# MCU.net
KiCad netlist of a schematic drawn in Altium Designer
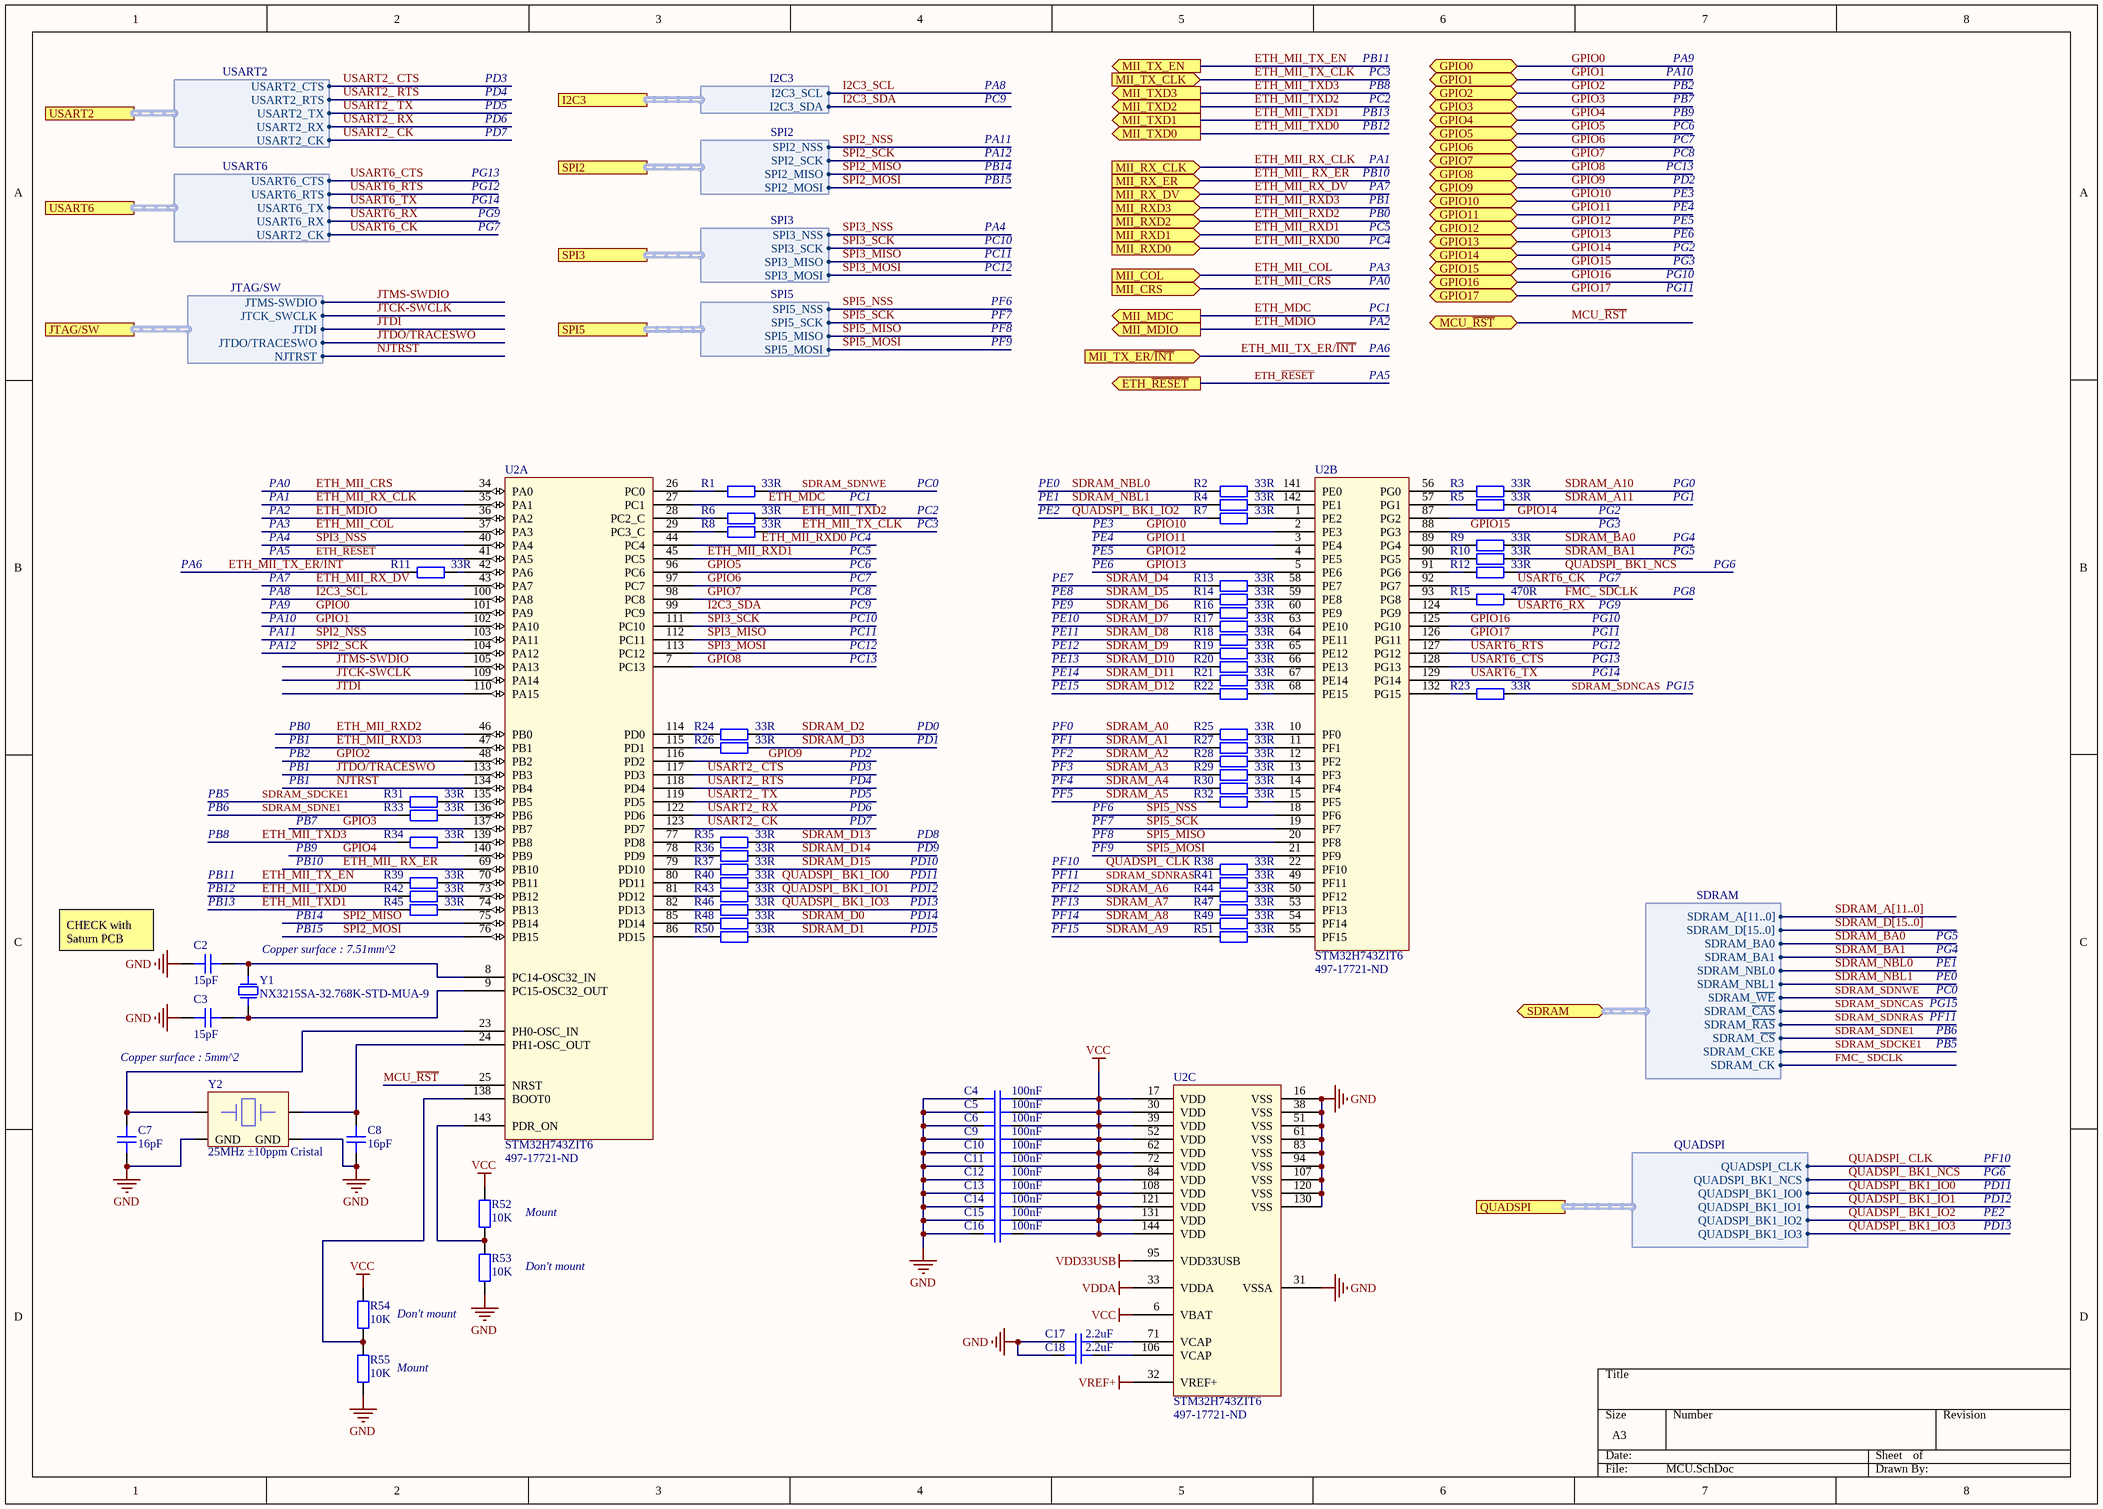
[diagram p0: MCU.SchDoc]

(export (version "E")
  (design (tool "Eeschema 10.0.6"))
  (components
    (comp (ref "C2")
      (value "15pF")
      (footprint "Capacitor-0603")
      (fields (field (name "Comment") "C-15pF-0603"))
      (libsource (lib "Components") (part "C-15pF-0603"))
    )
    (comp (ref "C3")
      (value "15pF")
      (footprint "Capacitor-0603")
      (fields (field (name "Comment") "C-15pF-0603"))
      (libsource (lib "Components") (part "C-15pF-0603"))
    )
    (comp (ref "C4")
      (value "100nF")
      (footprint "Capacitor-0603")
      (fields (field (name "Comment") "C-100nF-0603"))
      (libsource (lib "Components") (part "C-100nF-0603"))
    )
    (comp (ref "C5")
      (value "100nF")
      (footprint "Capacitor-0603")
      (fields (field (name "Comment") "C-100nF-0603"))
      (libsource (lib "Components") (part "C-100nF-0603"))
    )
    (comp (ref "C6")
      (value "100nF")
      (footprint "Capacitor-0603")
      (fields (field (name "Comment") "C-100nF-0603"))
      (libsource (lib "Components") (part "C-100nF-0603"))
    )
    (comp (ref "C7")
      (value "16pF")
      (footprint "Capacitor-0603")
      (fields (field (name "Comment") "C-16pF-0603"))
      (libsource (lib "Components") (part "C-16pF-0603"))
    )
    (comp (ref "C8")
      (value "16pF")
      (footprint "Capacitor-0603")
      (fields (field (name "Comment") "C-16pF-0603"))
      (libsource (lib "Components") (part "C-16pF-0603"))
    )
    (comp (ref "C9")
      (value "100nF")
      (footprint "Capacitor-0603")
      (fields (field (name "Comment") "C-100nF-0603"))
      (libsource (lib "Components") (part "C-100nF-0603"))
    )
    (comp (ref "C10")
      (value "100nF")
      (footprint "Capacitor-0603")
      (fields (field (name "Comment") "C-100nF-0603"))
      (libsource (lib "Components") (part "C-100nF-0603"))
    )
    (comp (ref "C11")
      (value "100nF")
      (footprint "Capacitor-0603")
      (fields (field (name "Comment") "C-100nF-0603"))
      (libsource (lib "Components") (part "C-100nF-0603"))
    )
    (comp (ref "C12")
      (value "100nF")
      (footprint "Capacitor-0603")
      (fields (field (name "Comment") "C-100nF-0603"))
      (libsource (lib "Components") (part "C-100nF-0603"))
    )
    (comp (ref "C13")
      (value "100nF")
      (footprint "Capacitor-0603")
      (fields (field (name "Comment") "C-100nF-0603"))
      (libsource (lib "Components") (part "C-100nF-0603"))
    )
    (comp (ref "C14")
      (value "100nF")
      (footprint "Capacitor-0603")
      (fields (field (name "Comment") "C-100nF-0603"))
      (libsource (lib "Components") (part "C-100nF-0603"))
    )
    (comp (ref "C15")
      (value "100nF")
      (footprint "Capacitor-0603")
      (fields (field (name "Comment") "C-100nF-0603"))
      (libsource (lib "Components") (part "C-100nF-0603"))
    )
    (comp (ref "C16")
      (value "100nF")
      (footprint "Capacitor-0603")
      (fields (field (name "Comment") "C-100nF-0603"))
      (libsource (lib "Components") (part "C-100nF-0603"))
    )
    (comp (ref "C17")
      (value "2.2uF")
      (footprint "Capacitor-0603")
      (fields (field (name "Comment") "C-2.2uF-0603"))
      (libsource (lib "Components") (part "C-2.2uF-0603"))
    )
    (comp (ref "C18")
      (value "2.2uF")
      (footprint "Capacitor-0603")
      (fields (field (name "Comment") "C-2.2uF-0603"))
      (libsource (lib "Components") (part "C-2.2uF-0603"))
    )
    (comp (ref "R1")
      (value "33R")
      (footprint "Resistor-0603")
      (fields (field (name "Comment") "R-33R-0603"))
      (libsource (lib "Components") (part "R-33R-0603"))
    )
    (comp (ref "R2")
      (value "33R")
      (footprint "Resistor-0603")
      (fields (field (name "Comment") "R-33R-0603"))
      (libsource (lib "Components") (part "R-33R-0603"))
    )
    (comp (ref "R3")
      (value "33R")
      (footprint "Resistor-0603")
      (fields (field (name "Comment") "R-33R-0603"))
      (libsource (lib "Components") (part "R-33R-0603"))
    )
    (comp (ref "R4")
      (value "33R")
      (footprint "Resistor-0603")
      (fields (field (name "Comment") "R-33R-0603"))
      (libsource (lib "Components") (part "R-33R-0603"))
    )
    (comp (ref "R5")
      (value "33R")
      (footprint "Resistor-0603")
      (fields (field (name "Comment") "R-33R-0603"))
      (libsource (lib "Components") (part "R-33R-0603"))
    )
    (comp (ref "R6")
      (value "33R")
      (footprint "Resistor-0603")
      (fields (field (name "Comment") "R-33R-0603"))
      (libsource (lib "Components") (part "R-33R-0603"))
    )
    (comp (ref "R7")
      (value "33R")
      (footprint "Resistor-0603")
      (fields (field (name "Comment") "R-33R-0603"))
      (libsource (lib "Components") (part "R-33R-0603"))
    )
    (comp (ref "R8")
      (value "33R")
      (footprint "Resistor-0603")
      (fields (field (name "Comment") "R-33R-0603"))
      (libsource (lib "Components") (part "R-33R-0603"))
    )
    (comp (ref "R9")
      (value "33R")
      (footprint "Resistor-0603")
      (fields (field (name "Comment") "R-33R-0603"))
      (libsource (lib "Components") (part "R-33R-0603"))
    )
    (comp (ref "R10")
      (value "33R")
      (footprint "Resistor-0603")
      (fields (field (name "Comment") "R-33R-0603"))
      (libsource (lib "Components") (part "R-33R-0603"))
    )
    (comp (ref "R11")
      (value "33R")
      (footprint "Resistor-0603")
      (fields (field (name "Comment") "R-33R-0603"))
      (libsource (lib "Components") (part "R-33R-0603"))
    )
    (comp (ref "R12")
      (value "33R")
      (footprint "Resistor-0603")
      (fields (field (name "Comment") "R-33R-0603"))
      (libsource (lib "Components") (part "R-33R-0603"))
    )
    (comp (ref "R13")
      (value "33R")
      (footprint "Resistor-0603")
      (fields (field (name "Comment") "R-33R-0603"))
      (libsource (lib "Components") (part "R-33R-0603"))
    )
    (comp (ref "R14")
      (value "33R")
      (footprint "Resistor-0603")
      (fields (field (name "Comment") "R-33R-0603"))
      (libsource (lib "Components") (part "R-33R-0603"))
    )
    (comp (ref "R15")
      (value "470R")
      (footprint "Resistor-0603")
      (fields (field (name "Comment") "R-470R-0603"))
      (libsource (lib "Components") (part "R-470R-0603"))
    )
    (comp (ref "R16")
      (value "33R")
      (footprint "Resistor-0603")
      (fields (field (name "Comment") "R-33R-0603"))
      (libsource (lib "Components") (part "R-33R-0603"))
    )
    (comp (ref "R17")
      (value "33R")
      (footprint "Resistor-0603")
      (fields (field (name "Comment") "R-33R-0603"))
      (libsource (lib "Components") (part "R-33R-0603"))
    )
    (comp (ref "R18")
      (value "33R")
      (footprint "Resistor-0603")
      (fields (field (name "Comment") "R-33R-0603"))
      (libsource (lib "Components") (part "R-33R-0603"))
    )
    (comp (ref "R19")
      (value "33R")
      (footprint "Resistor-0603")
      (fields (field (name "Comment") "R-33R-0603"))
      (libsource (lib "Components") (part "R-33R-0603"))
    )
    (comp (ref "R20")
      (value "33R")
      (footprint "Resistor-0603")
      (fields (field (name "Comment") "R-33R-0603"))
      (libsource (lib "Components") (part "R-33R-0603"))
    )
    (comp (ref "R21")
      (value "33R")
      (footprint "Resistor-0603")
      (fields (field (name "Comment") "R-33R-0603"))
      (libsource (lib "Components") (part "R-33R-0603"))
    )
    (comp (ref "R22")
      (value "33R")
      (footprint "Resistor-0603")
      (fields (field (name "Comment") "R-33R-0603"))
      (libsource (lib "Components") (part "R-33R-0603"))
    )
    (comp (ref "R23")
      (value "33R")
      (footprint "Resistor-0603")
      (fields (field (name "Comment") "R-33R-0603"))
      (libsource (lib "Components") (part "R-33R-0603"))
    )
    (comp (ref "R24")
      (value "33R")
      (footprint "Resistor-0603")
      (fields (field (name "Comment") "R-33R-0603"))
      (libsource (lib "Components") (part "R-33R-0603"))
    )
    (comp (ref "R25")
      (value "33R")
      (footprint "Resistor-0603")
      (fields (field (name "Comment") "R-33R-0603"))
      (libsource (lib "Components") (part "R-33R-0603"))
    )
    (comp (ref "R26")
      (value "33R")
      (footprint "Resistor-0603")
      (fields (field (name "Comment") "R-33R-0603"))
      (libsource (lib "Components") (part "R-33R-0603"))
    )
    (comp (ref "R27")
      (value "33R")
      (footprint "Resistor-0603")
      (fields (field (name "Comment") "R-33R-0603"))
      (libsource (lib "Components") (part "R-33R-0603"))
    )
    (comp (ref "R28")
      (value "33R")
      (footprint "Resistor-0603")
      (fields (field (name "Comment") "R-33R-0603"))
      (libsource (lib "Components") (part "R-33R-0603"))
    )
    (comp (ref "R29")
      (value "33R")
      (footprint "Resistor-0603")
      (fields (field (name "Comment") "R-33R-0603"))
      (libsource (lib "Components") (part "R-33R-0603"))
    )
    (comp (ref "R30")
      (value "33R")
      (footprint "Resistor-0603")
      (fields (field (name "Comment") "R-33R-0603"))
      (libsource (lib "Components") (part "R-33R-0603"))
    )
    (comp (ref "R31")
      (value "33R")
      (footprint "Resistor-0603")
      (fields (field (name "Comment") "R-33R-0603"))
      (libsource (lib "Components") (part "R-33R-0603"))
    )
    (comp (ref "R32")
      (value "33R")
      (footprint "Resistor-0603")
      (fields (field (name "Comment") "R-33R-0603"))
      (libsource (lib "Components") (part "R-33R-0603"))
    )
    (comp (ref "R33")
      (value "33R")
      (footprint "Resistor-0603")
      (fields (field (name "Comment") "R-33R-0603"))
      (libsource (lib "Components") (part "R-33R-0603"))
    )
    (comp (ref "R34")
      (value "33R")
      (footprint "Resistor-0603")
      (fields (field (name "Comment") "R-33R-0603"))
      (libsource (lib "Components") (part "R-33R-0603"))
    )
    (comp (ref "R35")
      (value "33R")
      (footprint "Resistor-0603")
      (fields (field (name "Comment") "R-33R-0603"))
      (libsource (lib "Components") (part "R-33R-0603"))
    )
    (comp (ref "R36")
      (value "33R")
      (footprint "Resistor-0603")
      (fields (field (name "Comment") "R-33R-0603"))
      (libsource (lib "Components") (part "R-33R-0603"))
    )
    (comp (ref "R37")
      (value "33R")
      (footprint "Resistor-0603")
      (fields (field (name "Comment") "R-33R-0603"))
      (libsource (lib "Components") (part "R-33R-0603"))
    )
    (comp (ref "R38")
      (value "33R")
      (footprint "Resistor-0603")
      (fields (field (name "Comment") "R-33R-0603"))
      (libsource (lib "Components") (part "R-33R-0603"))
    )
    (comp (ref "R39")
      (value "33R")
      (footprint "Resistor-0603")
      (fields (field (name "Comment") "R-33R-0603"))
      (libsource (lib "Components") (part "R-33R-0603"))
    )
    (comp (ref "R40")
      (value "33R")
      (footprint "Resistor-0603")
      (fields (field (name "Comment") "R-33R-0603"))
      (libsource (lib "Components") (part "R-33R-0603"))
    )
    (comp (ref "R41")
      (value "33R")
      (footprint "Resistor-0603")
      (fields (field (name "Comment") "R-33R-0603"))
      (libsource (lib "Components") (part "R-33R-0603"))
    )
    (comp (ref "R42")
      (value "33R")
      (footprint "Resistor-0603")
      (fields (field (name "Comment") "R-33R-0603"))
      (libsource (lib "Components") (part "R-33R-0603"))
    )
    (comp (ref "R43")
      (value "33R")
      (footprint "Resistor-0603")
      (fields (field (name "Comment") "R-33R-0603"))
      (libsource (lib "Components") (part "R-33R-0603"))
    )
    (comp (ref "R44")
      (value "33R")
      (footprint "Resistor-0603")
      (fields (field (name "Comment") "R-33R-0603"))
      (libsource (lib "Components") (part "R-33R-0603"))
    )
    (comp (ref "R45")
      (value "33R")
      (footprint "Resistor-0603")
      (fields (field (name "Comment") "R-33R-0603"))
      (libsource (lib "Components") (part "R-33R-0603"))
    )
    (comp (ref "R46")
      (value "33R")
      (footprint "Resistor-0603")
      (fields (field (name "Comment") "R-33R-0603"))
      (libsource (lib "Components") (part "R-33R-0603"))
    )
    (comp (ref "R47")
      (value "33R")
      (footprint "Resistor-0603")
      (fields (field (name "Comment") "R-33R-0603"))
      (libsource (lib "Components") (part "R-33R-0603"))
    )
    (comp (ref "R48")
      (value "33R")
      (footprint "Resistor-0603")
      (fields (field (name "Comment") "R-33R-0603"))
      (libsource (lib "Components") (part "R-33R-0603"))
    )
    (comp (ref "R49")
      (value "33R")
      (footprint "Resistor-0603")
      (fields (field (name "Comment") "R-33R-0603"))
      (libsource (lib "Components") (part "R-33R-0603"))
    )
    (comp (ref "R50")
      (value "33R")
      (footprint "Resistor-0603")
      (fields (field (name "Comment") "R-33R-0603"))
      (libsource (lib "Components") (part "R-33R-0603"))
    )
    (comp (ref "R51")
      (value "33R")
      (footprint "Resistor-0603")
      (fields (field (name "Comment") "R-33R-0603"))
      (libsource (lib "Components") (part "R-33R-0603"))
    )
    (comp (ref "R52")
      (value "10K")
      (footprint "Resistor-0603")
      (fields (field (name "Comment") "R-10K-0603"))
      (libsource (lib "Components") (part "R-10K-0603"))
    )
    (comp (ref "R53")
      (value "10K")
      (footprint "Resistor-0603")
      (fields (field (name "Comment") "R-10K-0603"))
      (libsource (lib "Components") (part "R-10K-0603"))
    )
    (comp (ref "R54")
      (value "10K")
      (footprint "Resistor-0603")
      (fields (field (name "Comment") "R-10K-0603"))
      (libsource (lib "Components") (part "R-10K-0603"))
    )
    (comp (ref "R55")
      (value "10K")
      (footprint "Resistor-0603")
      (fields (field (name "Comment") "R-10K-0603"))
      (libsource (lib "Components") (part "R-10K-0603"))
    )
    (comp (ref "U2")
      (value "STM32H743ZIT6")
      (footprint "STM32H743ZIT6")
      (fields (field (name "SUPPLIER PART NUMBER 1") "497-17721-ND"))
      (libsource (lib "Components") (part "STM32H743ZIT6"))
    )
    (comp (ref "Y1")
      (value "NX3215SA-32.768K-STD-MUA-9")
      (footprint "NX3215SA-32.768K-STD-MUA-9")
      (libsource (lib "Components") (part "NX3215SA-32.768K-STD-MUA-9"))
    )
    (comp (ref "Y2")
      (value "25MHz ±10ppm Cristal")
      (footprint "830107871909")
      (libsource (lib "Components") (part "830107871909"))
    )
  )
  (nets
    (net (code "10") (name "/ETH_MDC") (class "Default")
      (node (ref "U2") (pin "27") (pinfunction "PC1_27") (pintype "passive"))
    )
    (net (code "11") (name "/ETH_MDIO") (class "Default")
      (node (ref "U2") (pin "36") (pinfunction "PA2_36") (pintype "bidirectional"))
    )
    (net (code "12") (name "/ETH_MII_ RX_ER") (class "Default")
      (node (ref "U2") (pin "69") (pinfunction "PB10_69") (pintype "bidirectional"))
    )
    (net (code "13") (name "/ETH_MII_COL") (class "Default")
      (node (ref "U2") (pin "37") (pinfunction "PA3_37") (pintype "bidirectional"))
    )
    (net (code "14") (name "/ETH_MII_CRS") (class "Default")
      (node (ref "U2") (pin "34") (pinfunction "PA0_34") (pintype "bidirectional"))
    )
    (net (code "15") (name "/ETH_MII_RXD0") (class "Default")
      (node (ref "U2") (pin "44") (pinfunction "PC4_44") (pintype "passive"))
    )
    (net (code "16") (name "/ETH_MII_RXD1") (class "Default")
      (node (ref "U2") (pin "45") (pinfunction "PC5_45") (pintype "passive"))
    )
    (net (code "17") (name "/ETH_MII_RXD2") (class "Default")
      (node (ref "U2") (pin "46") (pinfunction "PB0_46") (pintype "bidirectional"))
    )
    (net (code "18") (name "/ETH_MII_RXD3") (class "Default")
      (node (ref "U2") (pin "47") (pinfunction "PB1_47") (pintype "bidirectional"))
    )
    (net (code "19") (name "/ETH_MII_RX_CLK") (class "Default")
      (node (ref "U2") (pin "35") (pinfunction "PA1_35") (pintype "bidirectional"))
    )
    (net (code "20") (name "/ETH_MII_RX_DV") (class "Default")
      (node (ref "U2") (pin "43") (pinfunction "PA7_43") (pintype "bidirectional"))
    )
    (net (code "21") (name "/ETH_MII_TXD0") (class "Default")
      (node (ref "R42") (pin "1") (pinfunction "1_1") (pintype "passive"))
    )
    (net (code "22") (name "/ETH_MII_TXD1") (class "Default")
      (node (ref "R45") (pin "1") (pinfunction "1_1") (pintype "passive"))
    )
    (net (code "23") (name "/ETH_MII_TXD2") (class "Default")
      (node (ref "R6") (pin "2") (pinfunction "2_2") (pintype "passive"))
    )
    (net (code "24") (name "/ETH_MII_TXD3") (class "Default")
      (node (ref "R34") (pin "1") (pinfunction "1_1") (pintype "passive"))
    )
    (net (code "25") (name "/ETH_MII_TX_CLK") (class "Default")
      (node (ref "R8") (pin "2") (pinfunction "2_2") (pintype "passive"))
    )
    (net (code "26") (name "/ETH_MII_TX_EN") (class "Default")
      (node (ref "R39") (pin "1") (pinfunction "1_1") (pintype "passive"))
    )
    (net (code "27") (name "/ETH_MII_TX_ER{slash}~{INT}") (class "Default")
      (node (ref "R11") (pin "1") (pinfunction "1_1") (pintype "passive"))
    )
    (net (code "28") (name "/ETH_~{RESET}") (class "Default")
      (node (ref "U2") (pin "41") (pinfunction "PA5_41") (pintype "bidirectional"))
    )
    (net (code "29") (name "/FMC_ SDCLK") (class "Default")
      (node (ref "R15") (pin "2") (pinfunction "2_2") (pintype "passive"))
    )
    (net (code "30") (name "/GPIO0") (class "Default")
      (node (ref "U2") (pin "101") (pinfunction "PA9_101") (pintype "bidirectional"))
    )
    (net (code "31") (name "/GPIO1") (class "Default")
      (node (ref "U2") (pin "102") (pinfunction "PA10_102") (pintype "bidirectional"))
    )
    (net (code "32") (name "/GPIO2") (class "Default")
      (node (ref "U2") (pin "48") (pinfunction "PB2_48") (pintype "bidirectional"))
    )
    (net (code "33") (name "/GPIO3") (class "Default")
      (node (ref "U2") (pin "137") (pinfunction "PB7_137") (pintype "bidirectional"))
    )
    (net (code "34") (name "/GPIO4") (class "Default")
      (node (ref "U2") (pin "140") (pinfunction "PB9_140") (pintype "bidirectional"))
    )
    (net (code "35") (name "/GPIO5") (class "Default")
      (node (ref "U2") (pin "96") (pinfunction "PC6_96") (pintype "passive"))
    )
    (net (code "36") (name "/GPIO6") (class "Default")
      (node (ref "U2") (pin "97") (pinfunction "PC7_97") (pintype "passive"))
    )
    (net (code "37") (name "/GPIO7") (class "Default")
      (node (ref "U2") (pin "98") (pinfunction "PC8_98") (pintype "passive"))
    )
    (net (code "38") (name "/GPIO8") (class "Default")
      (node (ref "U2") (pin "7") (pinfunction "PC13_7") (pintype "passive"))
    )
    (net (code "39") (name "/GPIO9") (class "Default")
      (node (ref "U2") (pin "116") (pinfunction "PD2_116") (pintype "passive"))
    )
    (net (code "40") (name "/GPIO10") (class "Default")
      (node (ref "U2") (pin "2") (pinfunction "PE3_2") (pintype "passive"))
    )
    (net (code "41") (name "/GPIO11") (class "Default")
      (node (ref "U2") (pin "3") (pinfunction "PE4_3") (pintype "passive"))
    )
    (net (code "42") (name "/GPIO12") (class "Default")
      (node (ref "U2") (pin "4") (pinfunction "PE5_4") (pintype "passive"))
    )
    (net (code "43") (name "/GPIO13") (class "Default")
      (node (ref "U2") (pin "5") (pinfunction "PE6_5") (pintype "passive"))
    )
    (net (code "44") (name "/GPIO14") (class "Default")
      (node (ref "U2") (pin "87") (pinfunction "PG2_87") (pintype "passive"))
    )
    (net (code "45") (name "/GPIO15") (class "Default")
      (node (ref "U2") (pin "88") (pinfunction "PG3_88") (pintype "passive"))
    )
    (net (code "46") (name "/GPIO16") (class "Default")
      (node (ref "U2") (pin "125") (pinfunction "PG10_125") (pintype "passive"))
    )
    (net (code "47") (name "/GPIO17") (class "Default")
      (node (ref "U2") (pin "126") (pinfunction "PG11_126") (pintype "passive"))
    )
    (net (code "48") (name "/I2C3_SCL") (class "Default")
      (node (ref "U2") (pin "100") (pinfunction "PA8_100") (pintype "bidirectional"))
    )
    (net (code "49") (name "/I2C3_SDA") (class "Default")
      (node (ref "U2") (pin "99") (pinfunction "PC9_99") (pintype "passive"))
    )
    (net (code "50") (name "/JTCK-SWCLK") (class "Default")
      (node (ref "U2") (pin "109") (pinfunction "PA14_109") (pintype "bidirectional"))
    )
    (net (code "51") (name "/JTDI") (class "Default")
      (node (ref "U2") (pin "110") (pinfunction "PA15_110") (pintype "bidirectional"))
    )
    (net (code "52") (name "/JTDO{slash}TRACESWO") (class "Default")
      (node (ref "U2") (pin "133") (pinfunction "PB3_133") (pintype "bidirectional"))
    )
    (net (code "53") (name "/JTMS-SWDIO") (class "Default")
      (node (ref "U2") (pin "105") (pinfunction "PA13_105") (pintype "bidirectional"))
    )
    (net (code "54") (name "/MCU_~{RST}") (class "Default")
      (node (ref "U2") (pin "25") (pinfunction "NRST_25") (pintype "passive"))
    )
    (net (code "55") (name "/NJTRST") (class "Default")
      (node (ref "U2") (pin "134") (pinfunction "PB4_134") (pintype "bidirectional"))
    )
    (net (code "56") (name "/QUADSPI_ BK1_IO0") (class "Default")
      (node (ref "R40") (pin "2") (pinfunction "2_2") (pintype "passive"))
    )
    (net (code "57") (name "/QUADSPI_ BK1_IO1") (class "Default")
      (node (ref "R43") (pin "2") (pinfunction "2_2") (pintype "passive"))
    )
    (net (code "58") (name "/QUADSPI_ BK1_IO2") (class "Default")
      (node (ref "R7") (pin "1") (pinfunction "1_1") (pintype "passive"))
    )
    (net (code "59") (name "/QUADSPI_ BK1_IO3") (class "Default")
      (node (ref "R46") (pin "2") (pinfunction "2_2") (pintype "passive"))
    )
    (net (code "60") (name "/QUADSPI_ BK1_NCS") (class "Default")
      (node (ref "R12") (pin "2") (pinfunction "2_2") (pintype "passive"))
    )
    (net (code "61") (name "/QUADSPI_ CLK") (class "Default")
      (node (ref "R38") (pin "1") (pinfunction "1_1") (pintype "passive"))
    )
    (net (code "62") (name "/SDRAM_A0") (class "Default")
      (node (ref "R25") (pin "1") (pinfunction "1_1") (pintype "passive"))
    )
    (net (code "63") (name "/SDRAM_A1") (class "Default")
      (node (ref "R27") (pin "1") (pinfunction "1_1") (pintype "passive"))
    )
    (net (code "64") (name "/SDRAM_A2") (class "Default")
      (node (ref "R28") (pin "1") (pinfunction "1_1") (pintype "passive"))
    )
    (net (code "65") (name "/SDRAM_A3") (class "Default")
      (node (ref "R29") (pin "1") (pinfunction "1_1") (pintype "passive"))
    )
    (net (code "66") (name "/SDRAM_A4") (class "Default")
      (node (ref "R30") (pin "1") (pinfunction "1_1") (pintype "passive"))
    )
    (net (code "67") (name "/SDRAM_A5") (class "Default")
      (node (ref "R32") (pin "1") (pinfunction "1_1") (pintype "passive"))
    )
    (net (code "68") (name "/SDRAM_A6") (class "Default")
      (node (ref "R44") (pin "1") (pinfunction "1_1") (pintype "passive"))
    )
    (net (code "69") (name "/SDRAM_A7") (class "Default")
      (node (ref "R47") (pin "1") (pinfunction "1_1") (pintype "passive"))
    )
    (net (code "70") (name "/SDRAM_A8") (class "Default")
      (node (ref "R49") (pin "1") (pinfunction "1_1") (pintype "passive"))
    )
    (net (code "71") (name "/SDRAM_A9") (class "Default")
      (node (ref "R51") (pin "1") (pinfunction "1_1") (pintype "passive"))
    )
    (net (code "72") (name "/SDRAM_A10") (class "Default")
      (node (ref "R3") (pin "2") (pinfunction "2_2") (pintype "passive"))
    )
    (net (code "73") (name "/SDRAM_A11") (class "Default")
      (node (ref "R5") (pin "2") (pinfunction "2_2") (pintype "passive"))
    )
    (net (code "75") (name "/SDRAM_BA0") (class "Default")
      (node (ref "R9") (pin "2") (pinfunction "2_2") (pintype "passive"))
    )
    (net (code "76") (name "/SDRAM_BA1") (class "Default")
      (node (ref "R10") (pin "2") (pinfunction "2_2") (pintype "passive"))
    )
    (net (code "77") (name "/SDRAM_D0") (class "Default")
      (node (ref "R48") (pin "2") (pinfunction "2_2") (pintype "passive"))
    )
    (net (code "78") (name "/SDRAM_D1") (class "Default")
      (node (ref "R50") (pin "2") (pinfunction "2_2") (pintype "passive"))
    )
    (net (code "79") (name "/SDRAM_D2") (class "Default")
      (node (ref "R24") (pin "2") (pinfunction "2_2") (pintype "passive"))
    )
    (net (code "80") (name "/SDRAM_D3") (class "Default")
      (node (ref "R26") (pin "2") (pinfunction "2_2") (pintype "passive"))
    )
    (net (code "81") (name "/SDRAM_D4") (class "Default")
      (node (ref "R13") (pin "1") (pinfunction "1_1") (pintype "passive"))
    )
    (net (code "82") (name "/SDRAM_D5") (class "Default")
      (node (ref "R14") (pin "1") (pinfunction "1_1") (pintype "passive"))
    )
    (net (code "83") (name "/SDRAM_D6") (class "Default")
      (node (ref "R16") (pin "1") (pinfunction "1_1") (pintype "passive"))
    )
    (net (code "84") (name "/SDRAM_D7") (class "Default")
      (node (ref "R17") (pin "1") (pinfunction "1_1") (pintype "passive"))
    )
    (net (code "85") (name "/SDRAM_D8") (class "Default")
      (node (ref "R18") (pin "1") (pinfunction "1_1") (pintype "passive"))
    )
    (net (code "86") (name "/SDRAM_D9") (class "Default")
      (node (ref "R19") (pin "1") (pinfunction "1_1") (pintype "passive"))
    )
    (net (code "87") (name "/SDRAM_D10") (class "Default")
      (node (ref "R20") (pin "1") (pinfunction "1_1") (pintype "passive"))
    )
    (net (code "88") (name "/SDRAM_D11") (class "Default")
      (node (ref "R21") (pin "1") (pinfunction "1_1") (pintype "passive"))
    )
    (net (code "89") (name "/SDRAM_D12") (class "Default")
      (node (ref "R22") (pin "1") (pinfunction "1_1") (pintype "passive"))
    )
    (net (code "90") (name "/SDRAM_D13") (class "Default")
      (node (ref "R35") (pin "2") (pinfunction "2_2") (pintype "passive"))
    )
    (net (code "91") (name "/SDRAM_D14") (class "Default")
      (node (ref "R36") (pin "2") (pinfunction "2_2") (pintype "passive"))
    )
    (net (code "92") (name "/SDRAM_D15") (class "Default")
      (node (ref "R37") (pin "2") (pinfunction "2_2") (pintype "passive"))
    )
    (net (code "94") (name "/SDRAM_NBL0") (class "Default")
      (node (ref "R2") (pin "1") (pinfunction "1_1") (pintype "passive"))
    )
    (net (code "95") (name "/SDRAM_NBL1") (class "Default")
      (node (ref "R4") (pin "1") (pinfunction "1_1") (pintype "passive"))
    )
    (net (code "96") (name "/SDRAM_SDCKE1") (class "Default")
      (node (ref "R31") (pin "1") (pinfunction "1_1") (pintype "passive"))
    )
    (net (code "97") (name "/SDRAM_SDNCAS") (class "Default")
      (node (ref "R23") (pin "2") (pinfunction "2_2") (pintype "passive"))
    )
    (net (code "98") (name "/SDRAM_SDNE1") (class "Default")
      (node (ref "R33") (pin "1") (pinfunction "1_1") (pintype "passive"))
    )
    (net (code "99") (name "/SDRAM_SDNRAS") (class "Default")
      (node (ref "R41") (pin "1") (pinfunction "1_1") (pintype "passive"))
    )
    (net (code "100") (name "/SDRAM_SDNWE") (class "Default")
      (node (ref "R1") (pin "2") (pinfunction "2_2") (pintype "passive"))
    )
    (net (code "101") (name "/SPI2_MISO") (class "Default")
      (node (ref "U2") (pin "75") (pinfunction "PB14_75") (pintype "bidirectional"))
    )
    (net (code "102") (name "/SPI2_MOSI") (class "Default")
      (node (ref "U2") (pin "76") (pinfunction "PB15_76") (pintype "bidirectional"))
    )
    (net (code "103") (name "/SPI2_NSS") (class "Default")
      (node (ref "U2") (pin "103") (pinfunction "PA11_103") (pintype "bidirectional"))
    )
    (net (code "104") (name "/SPI2_SCK") (class "Default")
      (node (ref "U2") (pin "104") (pinfunction "PA12_104") (pintype "bidirectional"))
    )
    (net (code "105") (name "/SPI3_MISO") (class "Default")
      (node (ref "U2") (pin "112") (pinfunction "PC11_112") (pintype "passive"))
    )
    (net (code "106") (name "/SPI3_MOSI") (class "Default")
      (node (ref "U2") (pin "113") (pinfunction "PC12_113") (pintype "passive"))
    )
    (net (code "107") (name "/SPI3_NSS") (class "Default")
      (node (ref "U2") (pin "40") (pinfunction "PA4_40") (pintype "bidirectional"))
    )
    (net (code "108") (name "/SPI3_SCK") (class "Default")
      (node (ref "U2") (pin "111") (pinfunction "PC10_111") (pintype "passive"))
    )
    (net (code "109") (name "/SPI5_MISO") (class "Default")
      (node (ref "U2") (pin "20") (pinfunction "PF8_20") (pintype "passive"))
    )
    (net (code "110") (name "/SPI5_MOSI") (class "Default")
      (node (ref "U2") (pin "21") (pinfunction "PF9_21") (pintype "passive"))
    )
    (net (code "111") (name "/SPI5_NSS") (class "Default")
      (node (ref "U2") (pin "18") (pinfunction "PF6_18") (pintype "passive"))
    )
    (net (code "112") (name "/SPI5_SCK") (class "Default")
      (node (ref "U2") (pin "19") (pinfunction "PF7_19") (pintype "passive"))
    )
    (net (code "113") (name "/USART2_ CK") (class "Default")
      (node (ref "U2") (pin "123") (pinfunction "PD7_123") (pintype "passive"))
    )
    (net (code "114") (name "/USART2_ CTS") (class "Default")
      (node (ref "U2") (pin "117") (pinfunction "PD3_117") (pintype "passive"))
    )
    (net (code "115") (name "/USART2_ RTS") (class "Default")
      (node (ref "U2") (pin "118") (pinfunction "PD4_118") (pintype "passive"))
    )
    (net (code "116") (name "/USART2_ RX") (class "Default")
      (node (ref "U2") (pin "122") (pinfunction "PD6_122") (pintype "passive"))
    )
    (net (code "117") (name "/USART2_ TX") (class "Default")
      (node (ref "U2") (pin "119") (pinfunction "PD5_119") (pintype "passive"))
    )
    (net (code "118") (name "/USART6_CK") (class "Default")
      (node (ref "U2") (pin "92") (pinfunction "PG7_92") (pintype "passive"))
    )
    (net (code "119") (name "/USART6_CTS") (class "Default")
      (node (ref "U2") (pin "128") (pinfunction "PG13_128") (pintype "passive"))
    )
    (net (code "120") (name "/USART6_RTS") (class "Default")
      (node (ref "U2") (pin "127") (pinfunction "PG12_127") (pintype "passive"))
    )
    (net (code "121") (name "/USART6_RX") (class "Default")
      (node (ref "U2") (pin "124") (pinfunction "PG9_124") (pintype "passive"))
    )
    (net (code "122") (name "/USART6_TX") (class "Default")
      (node (ref "U2") (pin "129") (pinfunction "PG14_129") (pintype "passive"))
    )
    (net (code "132") (name "GND") (class "Default")
      (node (ref "C10") (pin "1") (pinfunction "1_1") (pintype "passive"))
      (node (ref "C11") (pin "1") (pinfunction "1_1") (pintype "passive"))
      (node (ref "C12") (pin "1") (pinfunction "1_1") (pintype "passive"))
      (node (ref "C13") (pin "1") (pinfunction "1_1") (pintype "passive"))
      (node (ref "C14") (pin "1") (pinfunction "1_1") (pintype "passive"))
      (node (ref "C15") (pin "1") (pinfunction "1_1") (pintype "passive"))
      (node (ref "C16") (pin "1") (pinfunction "1_1") (pintype "passive"))
      (node (ref "C17") (pin "1") (pinfunction "1_1") (pintype "passive"))
      (node (ref "C18") (pin "1") (pinfunction "1_1") (pintype "passive"))
      (node (ref "C2") (pin "1") (pinfunction "1_1") (pintype "passive"))
      (node (ref "C3") (pin "1") (pinfunction "1_1") (pintype "passive"))
      (node (ref "C4") (pin "1") (pinfunction "1_1") (pintype "passive"))
      (node (ref "C5") (pin "1") (pinfunction "1_1") (pintype "passive"))
      (node (ref "C6") (pin "1") (pinfunction "1_1") (pintype "passive"))
      (node (ref "C7") (pin "1") (pinfunction "1_1") (pintype "passive"))
      (node (ref "C8") (pin "1") (pinfunction "1_1") (pintype "passive"))
      (node (ref "C9") (pin "1") (pinfunction "1_1") (pintype "passive"))
      (node (ref "R53") (pin "1") (pinfunction "1_1") (pintype "passive"))
      (node (ref "R55") (pin "1") (pinfunction "1_1") (pintype "passive"))
      (node (ref "U2") (pin "107") (pinfunction "VSS_107") (pintype "passive"))
      (node (ref "U2") (pin "120") (pinfunction "VSS_120") (pintype "passive"))
      (node (ref "U2") (pin "130") (pinfunction "VSS_130") (pintype "passive"))
      (node (ref "U2") (pin "16") (pinfunction "VSS_16") (pintype "passive"))
      (node (ref "U2") (pin "31") (pinfunction "VSSA_31") (pintype "passive"))
      (node (ref "U2") (pin "38") (pinfunction "VSS_38") (pintype "passive"))
      (node (ref "U2") (pin "51") (pinfunction "VSS_51") (pintype "passive"))
      (node (ref "U2") (pin "61") (pinfunction "VSS_61") (pintype "passive"))
      (node (ref "U2") (pin "83") (pinfunction "VSS_83") (pintype "passive"))
      (node (ref "U2") (pin "94") (pinfunction "VSS_94") (pintype "passive"))
      (node (ref "Y2") (pin "2") (pinfunction "GND_2") (pintype "passive"))
      (node (ref "Y2") (pin "4") (pinfunction "GND_4") (pintype "passive"))
    )
    (net (code "133") (name "Net-(C17-Pad2)") (class "Default")
      (node (ref "C17") (pin "2") (pinfunction "2_2") (pintype "passive"))
      (node (ref "U2") (pin "71") (pinfunction "VCAP_71") (pintype "passive"))
    )
    (net (code "134") (name "Net-(C18-Pad2)") (class "Default")
      (node (ref "C18") (pin "2") (pinfunction "2_2") (pintype "passive"))
      (node (ref "U2") (pin "106") (pinfunction "VCAP_106") (pintype "passive"))
    )
    (net (code "135") (name "Net-(U2A-BOOT0)") (class "Default")
      (node (ref "R54") (pin "1") (pinfunction "1_1") (pintype "passive"))
      (node (ref "R55") (pin "2") (pinfunction "2_2") (pintype "passive"))
      (node (ref "U2") (pin "138") (pinfunction "BOOT0_138") (pintype "passive"))
    )
    (net (code "136") (name "Net-(U2A-PA6)") (class "Default")
      (node (ref "R11") (pin "2") (pinfunction "2_2") (pintype "passive"))
      (node (ref "U2") (pin "42") (pinfunction "PA6_42") (pintype "bidirectional"))
    )
    (net (code "137") (name "Net-(U2A-PB5)") (class "Default")
      (node (ref "R31") (pin "2") (pinfunction "2_2") (pintype "passive"))
      (node (ref "U2") (pin "135") (pinfunction "PB5_135") (pintype "bidirectional"))
    )
    (net (code "138") (name "Net-(U2A-PB6)") (class "Default")
      (node (ref "R33") (pin "2") (pinfunction "2_2") (pintype "passive"))
      (node (ref "U2") (pin "136") (pinfunction "PB6_136") (pintype "bidirectional"))
    )
    (net (code "139") (name "Net-(U2A-PB8)") (class "Default")
      (node (ref "R34") (pin "2") (pinfunction "2_2") (pintype "passive"))
      (node (ref "U2") (pin "139") (pinfunction "PB8_139") (pintype "bidirectional"))
    )
    (net (code "140") (name "Net-(U2A-PB11)") (class "Default")
      (node (ref "R39") (pin "2") (pinfunction "2_2") (pintype "passive"))
      (node (ref "U2") (pin "70") (pinfunction "PB11_70") (pintype "bidirectional"))
    )
    (net (code "141") (name "Net-(U2A-PB12)") (class "Default")
      (node (ref "R42") (pin "2") (pinfunction "2_2") (pintype "passive"))
      (node (ref "U2") (pin "73") (pinfunction "PB12_73") (pintype "bidirectional"))
    )
    (net (code "142") (name "Net-(U2A-PB13)") (class "Default")
      (node (ref "R45") (pin "2") (pinfunction "2_2") (pintype "passive"))
      (node (ref "U2") (pin "74") (pinfunction "PB13_74") (pintype "bidirectional"))
    )
    (net (code "143") (name "Net-(U2A-PC0)") (class "Default")
      (node (ref "R1") (pin "1") (pinfunction "1_1") (pintype "passive"))
      (node (ref "U2") (pin "26") (pinfunction "PC0_26") (pintype "passive"))
    )
    (net (code "144") (name "Net-(U2A-PC2_C)") (class "Default")
      (node (ref "R6") (pin "1") (pinfunction "1_1") (pintype "passive"))
      (node (ref "U2") (pin "28") (pinfunction "PC2_C_28") (pintype "passive"))
    )
    (net (code "145") (name "Net-(U2A-PC3_C)") (class "Default")
      (node (ref "R8") (pin "1") (pinfunction "1_1") (pintype "passive"))
      (node (ref "U2") (pin "29") (pinfunction "PC3_C_29") (pintype "passive"))
    )
    (net (code "146") (name "Net-(U2A-PC14-OSC32_IN)") (class "Default")
      (node (ref "C2") (pin "2") (pinfunction "2_2") (pintype "passive"))
      (node (ref "U2") (pin "8") (pinfunction "PC14-OSC32_IN_8") (pintype "passive"))
      (node (ref "Y1") (pin "2") (pinfunction "2_2") (pintype "passive"))
    )
    (net (code "147") (name "Net-(U2A-PC15-OSC32_OUT)") (class "Default")
      (node (ref "C3") (pin "2") (pinfunction "2_2") (pintype "passive"))
      (node (ref "U2") (pin "9") (pinfunction "PC15-OSC32_OUT_9") (pintype "passive"))
      (node (ref "Y1") (pin "1") (pinfunction "1_1") (pintype "passive"))
    )
    (net (code "148") (name "Net-(U2A-PD0)") (class "Default")
      (node (ref "R24") (pin "1") (pinfunction "1_1") (pintype "passive"))
      (node (ref "U2") (pin "114") (pinfunction "PD0_114") (pintype "passive"))
    )
    (net (code "149") (name "Net-(U2A-PD1)") (class "Default")
      (node (ref "R26") (pin "1") (pinfunction "1_1") (pintype "passive"))
      (node (ref "U2") (pin "115") (pinfunction "PD1_115") (pintype "passive"))
    )
    (net (code "150") (name "Net-(U2A-PD8)") (class "Default")
      (node (ref "R35") (pin "1") (pinfunction "1_1") (pintype "passive"))
      (node (ref "U2") (pin "77") (pinfunction "PD8_77") (pintype "passive"))
    )
    (net (code "151") (name "Net-(U2A-PD9)") (class "Default")
      (node (ref "R36") (pin "1") (pinfunction "1_1") (pintype "passive"))
      (node (ref "U2") (pin "78") (pinfunction "PD9_78") (pintype "passive"))
    )
    (net (code "152") (name "Net-(U2A-PD10)") (class "Default")
      (node (ref "R37") (pin "1") (pinfunction "1_1") (pintype "passive"))
      (node (ref "U2") (pin "79") (pinfunction "PD10_79") (pintype "passive"))
    )
    (net (code "153") (name "Net-(U2A-PD11)") (class "Default")
      (node (ref "R40") (pin "1") (pinfunction "1_1") (pintype "passive"))
      (node (ref "U2") (pin "80") (pinfunction "PD11_80") (pintype "passive"))
    )
    (net (code "154") (name "Net-(U2A-PD12)") (class "Default")
      (node (ref "R43") (pin "1") (pinfunction "1_1") (pintype "passive"))
      (node (ref "U2") (pin "81") (pinfunction "PD12_81") (pintype "passive"))
    )
    (net (code "155") (name "Net-(U2A-PD13)") (class "Default")
      (node (ref "R46") (pin "1") (pinfunction "1_1") (pintype "passive"))
      (node (ref "U2") (pin "82") (pinfunction "PD13_82") (pintype "passive"))
    )
    (net (code "156") (name "Net-(U2A-PD14)") (class "Default")
      (node (ref "R48") (pin "1") (pinfunction "1_1") (pintype "passive"))
      (node (ref "U2") (pin "85") (pinfunction "PD14_85") (pintype "passive"))
    )
    (net (code "157") (name "Net-(U2A-PD15)") (class "Default")
      (node (ref "R50") (pin "1") (pinfunction "1_1") (pintype "passive"))
      (node (ref "U2") (pin "86") (pinfunction "PD15_86") (pintype "passive"))
    )
    (net (code "158") (name "Net-(U2A-PDR_ON)") (class "Default")
      (node (ref "R52") (pin "1") (pinfunction "1_1") (pintype "passive"))
      (node (ref "R53") (pin "2") (pinfunction "2_2") (pintype "passive"))
      (node (ref "U2") (pin "143") (pinfunction "PDR_ON_143") (pintype "passive"))
    )
    (net (code "159") (name "Net-(U2A-PH0-OSC_IN)") (class "Default")
      (node (ref "C7") (pin "2") (pinfunction "2_2") (pintype "passive"))
      (node (ref "U2") (pin "23") (pinfunction "PH0-OSC_IN_23") (pintype "passive"))
      (node (ref "Y2") (pin "1") (pinfunction "GND_1") (pintype "passive"))
    )
    (net (code "160") (name "Net-(U2A-PH1-OSC_OUT)") (class "Default")
      (node (ref "C8") (pin "2") (pinfunction "2_2") (pintype "passive"))
      (node (ref "U2") (pin "24") (pinfunction "PH1-OSC_OUT_24") (pintype "passive"))
      (node (ref "Y2") (pin "3") (pinfunction "XTAL2_3") (pintype "passive"))
    )
    (net (code "161") (name "Net-(U2B-PE0)") (class "Default")
      (node (ref "R2") (pin "2") (pinfunction "2_2") (pintype "passive"))
      (node (ref "U2") (pin "141") (pinfunction "PE0_141") (pintype "passive"))
    )
    (net (code "162") (name "Net-(U2B-PE1)") (class "Default")
      (node (ref "R4") (pin "2") (pinfunction "2_2") (pintype "passive"))
      (node (ref "U2") (pin "142") (pinfunction "PE1_142") (pintype "passive"))
    )
    (net (code "163") (name "Net-(U2B-PE2)") (class "Default")
      (node (ref "R7") (pin "2") (pinfunction "2_2") (pintype "passive"))
      (node (ref "U2") (pin "1") (pinfunction "PE2_1") (pintype "passive"))
    )
    (net (code "164") (name "Net-(U2B-PE7)") (class "Default")
      (node (ref "R13") (pin "2") (pinfunction "2_2") (pintype "passive"))
      (node (ref "U2") (pin "58") (pinfunction "PE7_58") (pintype "passive"))
    )
    (net (code "165") (name "Net-(U2B-PE8)") (class "Default")
      (node (ref "R14") (pin "2") (pinfunction "2_2") (pintype "passive"))
      (node (ref "U2") (pin "59") (pinfunction "PE8_59") (pintype "passive"))
    )
    (net (code "166") (name "Net-(U2B-PE9)") (class "Default")
      (node (ref "R16") (pin "2") (pinfunction "2_2") (pintype "passive"))
      (node (ref "U2") (pin "60") (pinfunction "PE9_60") (pintype "passive"))
    )
    (net (code "167") (name "Net-(U2B-PE10)") (class "Default")
      (node (ref "R17") (pin "2") (pinfunction "2_2") (pintype "passive"))
      (node (ref "U2") (pin "63") (pinfunction "PE10_63") (pintype "passive"))
    )
    (net (code "168") (name "Net-(U2B-PE11)") (class "Default")
      (node (ref "R18") (pin "2") (pinfunction "2_2") (pintype "passive"))
      (node (ref "U2") (pin "64") (pinfunction "PE11_64") (pintype "passive"))
    )
    (net (code "169") (name "Net-(U2B-PE12)") (class "Default")
      (node (ref "R19") (pin "2") (pinfunction "2_2") (pintype "passive"))
      (node (ref "U2") (pin "65") (pinfunction "PE12_65") (pintype "passive"))
    )
    (net (code "170") (name "Net-(U2B-PE13)") (class "Default")
      (node (ref "R20") (pin "2") (pinfunction "2_2") (pintype "passive"))
      (node (ref "U2") (pin "66") (pinfunction "PE13_66") (pintype "passive"))
    )
    (net (code "171") (name "Net-(U2B-PE14)") (class "Default")
      (node (ref "R21") (pin "2") (pinfunction "2_2") (pintype "passive"))
      (node (ref "U2") (pin "67") (pinfunction "PE14_67") (pintype "passive"))
    )
    (net (code "172") (name "Net-(U2B-PE15)") (class "Default")
      (node (ref "R22") (pin "2") (pinfunction "2_2") (pintype "passive"))
      (node (ref "U2") (pin "68") (pinfunction "PE15_68") (pintype "passive"))
    )
    (net (code "173") (name "Net-(U2B-PF0)") (class "Default")
      (node (ref "R25") (pin "2") (pinfunction "2_2") (pintype "passive"))
      (node (ref "U2") (pin "10") (pinfunction "PF0_10") (pintype "passive"))
    )
    (net (code "174") (name "Net-(U2B-PF1)") (class "Default")
      (node (ref "R27") (pin "2") (pinfunction "2_2") (pintype "passive"))
      (node (ref "U2") (pin "11") (pinfunction "PF1_11") (pintype "passive"))
    )
    (net (code "175") (name "Net-(U2B-PF2)") (class "Default")
      (node (ref "R28") (pin "2") (pinfunction "2_2") (pintype "passive"))
      (node (ref "U2") (pin "12") (pinfunction "PF2_12") (pintype "passive"))
    )
    (net (code "176") (name "Net-(U2B-PF3)") (class "Default")
      (node (ref "R29") (pin "2") (pinfunction "2_2") (pintype "passive"))
      (node (ref "U2") (pin "13") (pinfunction "PF3_13") (pintype "passive"))
    )
    (net (code "177") (name "Net-(U2B-PF4)") (class "Default")
      (node (ref "R30") (pin "2") (pinfunction "2_2") (pintype "passive"))
      (node (ref "U2") (pin "14") (pinfunction "PF4_14") (pintype "passive"))
    )
    (net (code "178") (name "Net-(U2B-PF5)") (class "Default")
      (node (ref "R32") (pin "2") (pinfunction "2_2") (pintype "passive"))
      (node (ref "U2") (pin "15") (pinfunction "PF5_15") (pintype "passive"))
    )
    (net (code "179") (name "Net-(U2B-PF10)") (class "Default")
      (node (ref "R38") (pin "2") (pinfunction "2_2") (pintype "passive"))
      (node (ref "U2") (pin "22") (pinfunction "PF10_22") (pintype "passive"))
    )
    (net (code "180") (name "Net-(U2B-PF11)") (class "Default")
      (node (ref "R41") (pin "2") (pinfunction "2_2") (pintype "passive"))
      (node (ref "U2") (pin "49") (pinfunction "PF11_49") (pintype "passive"))
    )
    (net (code "181") (name "Net-(U2B-PF12)") (class "Default")
      (node (ref "R44") (pin "2") (pinfunction "2_2") (pintype "passive"))
      (node (ref "U2") (pin "50") (pinfunction "PF12_50") (pintype "passive"))
    )
    (net (code "182") (name "Net-(U2B-PF13)") (class "Default")
      (node (ref "R47") (pin "2") (pinfunction "2_2") (pintype "passive"))
      (node (ref "U2") (pin "53") (pinfunction "PF13_53") (pintype "passive"))
    )
    (net (code "183") (name "Net-(U2B-PF14)") (class "Default")
      (node (ref "R49") (pin "2") (pinfunction "2_2") (pintype "passive"))
      (node (ref "U2") (pin "54") (pinfunction "PF14_54") (pintype "passive"))
    )
    (net (code "184") (name "Net-(U2B-PF15)") (class "Default")
      (node (ref "R51") (pin "2") (pinfunction "2_2") (pintype "passive"))
      (node (ref "U2") (pin "55") (pinfunction "PF15_55") (pintype "passive"))
    )
    (net (code "185") (name "Net-(U2B-PG0)") (class "Default")
      (node (ref "R3") (pin "1") (pinfunction "1_1") (pintype "passive"))
      (node (ref "U2") (pin "56") (pinfunction "PG0_56") (pintype "passive"))
    )
    (net (code "186") (name "Net-(U2B-PG1)") (class "Default")
      (node (ref "R5") (pin "1") (pinfunction "1_1") (pintype "passive"))
      (node (ref "U2") (pin "57") (pinfunction "PG1_57") (pintype "passive"))
    )
    (net (code "187") (name "Net-(U2B-PG4)") (class "Default")
      (node (ref "R9") (pin "1") (pinfunction "1_1") (pintype "passive"))
      (node (ref "U2") (pin "89") (pinfunction "PG4_89") (pintype "passive"))
    )
    (net (code "188") (name "Net-(U2B-PG5)") (class "Default")
      (node (ref "R10") (pin "1") (pinfunction "1_1") (pintype "passive"))
      (node (ref "U2") (pin "90") (pinfunction "PG5_90") (pintype "passive"))
    )
    (net (code "189") (name "Net-(U2B-PG6)") (class "Default")
      (node (ref "R12") (pin "1") (pinfunction "1_1") (pintype "passive"))
      (node (ref "U2") (pin "91") (pinfunction "PG6_91") (pintype "passive"))
    )
    (net (code "190") (name "Net-(U2B-PG8)") (class "Default")
      (node (ref "R15") (pin "1") (pinfunction "1_1") (pintype "passive"))
      (node (ref "U2") (pin "93") (pinfunction "PG8_93") (pintype "passive"))
    )
    (net (code "191") (name "Net-(U2B-PG15)") (class "Default")
      (node (ref "R23") (pin "1") (pinfunction "1_1") (pintype "passive"))
      (node (ref "U2") (pin "132") (pinfunction "PG15_132") (pintype "passive"))
    )
    (net (code "192") (name "VCC") (class "Default")
      (node (ref "C10") (pin "2") (pinfunction "2_2") (pintype "passive"))
      (node (ref "C11") (pin "2") (pinfunction "2_2") (pintype "passive"))
      (node (ref "C12") (pin "2") (pinfunction "2_2") (pintype "passive"))
      (node (ref "C13") (pin "2") (pinfunction "2_2") (pintype "passive"))
      (node (ref "C14") (pin "2") (pinfunction "2_2") (pintype "passive"))
      (node (ref "C15") (pin "2") (pinfunction "2_2") (pintype "passive"))
      (node (ref "C16") (pin "2") (pinfunction "2_2") (pintype "passive"))
      (node (ref "C4") (pin "2") (pinfunction "2_2") (pintype "passive"))
      (node (ref "C5") (pin "2") (pinfunction "2_2") (pintype "passive"))
      (node (ref "C6") (pin "2") (pinfunction "2_2") (pintype "passive"))
      (node (ref "C9") (pin "2") (pinfunction "2_2") (pintype "passive"))
      (node (ref "R52") (pin "2") (pinfunction "2_2") (pintype "passive"))
      (node (ref "R54") (pin "2") (pinfunction "2_2") (pintype "passive"))
      (node (ref "U2") (pin "108") (pinfunction "VDD_108") (pintype "passive"))
      (node (ref "U2") (pin "121") (pinfunction "VDD_121") (pintype "passive"))
      (node (ref "U2") (pin "131") (pinfunction "VDD_131") (pintype "passive"))
      (node (ref "U2") (pin "144") (pinfunction "VDD_144") (pintype "passive"))
      (node (ref "U2") (pin "17") (pinfunction "VDD_17") (pintype "passive"))
      (node (ref "U2") (pin "30") (pinfunction "VDD_30") (pintype "passive"))
      (node (ref "U2") (pin "39") (pinfunction "VDD_39") (pintype "passive"))
      (node (ref "U2") (pin "52") (pinfunction "VDD_52") (pintype "passive"))
      (node (ref "U2") (pin "6") (pinfunction "VBAT_6") (pintype "passive"))
      (node (ref "U2") (pin "62") (pinfunction "VDD_62") (pintype "passive"))
      (node (ref "U2") (pin "72") (pinfunction "VDD_72") (pintype "passive"))
      (node (ref "U2") (pin "84") (pinfunction "VDD_84") (pintype "passive"))
    )
    (net (code "193") (name "VDD33USB") (class "Default")
      (node (ref "U2") (pin "95") (pinfunction "VDD33USB_95") (pintype "passive"))
    )
    (net (code "194") (name "VDDA") (class "Default")
      (node (ref "U2") (pin "33") (pinfunction "VDDA_33") (pintype "passive"))
    )
    (net (code "195") (name "VREF+") (class "Default")
      (node (ref "U2") (pin "32") (pinfunction "VREF+_32") (pintype "passive"))
    )
  )
)
